# fuse-a-3.net
KiCad netlist of a schematic drawn in EAGLE
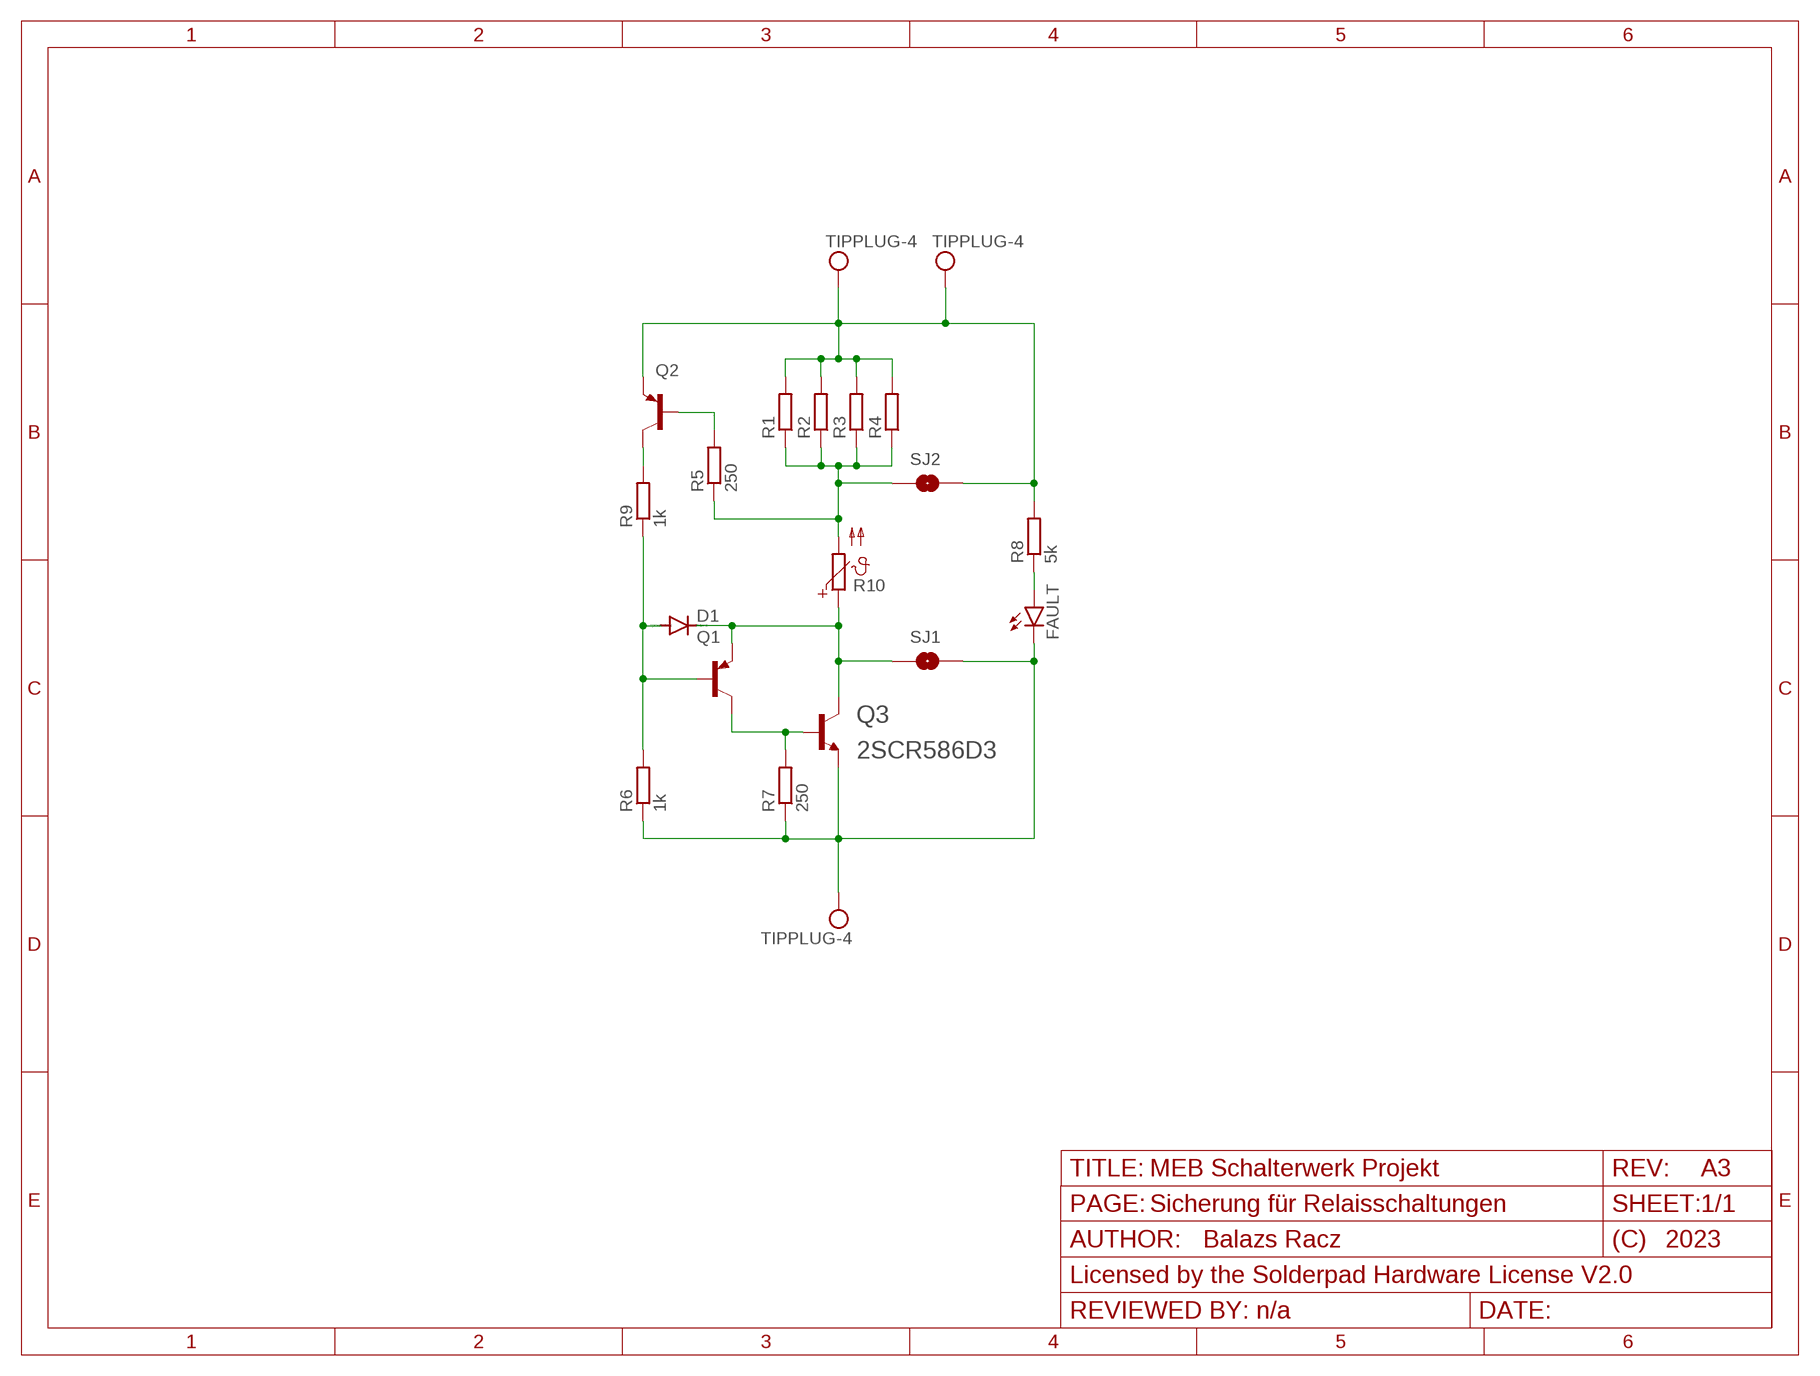
[diagram p0: schematic, sheet 1]

(export (version "E")
  (design (tool "Eeschema 10.0.6"))
  (components
    (comp (ref "D1")
      (value "DIODE-MINIMELF")
      (footprint "eagle-import:MINIMELF")
      (libsource (lib "eagle-import") (part "DIODE-MINIMELF"))
    )
    (comp (ref "FAULT")
      (value "LEDCHIPLED_0603")
      (footprint "eagle-import:CHIPLED_0603")
      (libsource (lib "eagle-import") (part "LEDCHIPLED_0603"))
    )
    (comp (ref "Q1")
      (value "BCX71SMD")
      (footprint "eagle-import:SOT23")
      (libsource (lib "eagle-import") (part "BCX71SMD"))
    )
    (comp (ref "Q2")
      (value "BCX71SMD")
      (footprint "eagle-import:SOT23")
      (libsource (lib "eagle-import") (part "BCX71SMD"))
    )
    (comp (ref "Q3")
      (value "2SCR586D3")
      (footprint "eagle-import:D-PAK_TO252AA")
      (libsource (lib "eagle-import") (part "2SCR586D3TL1"))
    )
    (comp (ref "R1")
      (value "R-EU_R2512")
      (footprint "eagle-import:R2512")
      (libsource (lib "eagle-import") (part "R-EU_R2512"))
    )
    (comp (ref "R2")
      (value "R-EU_R2512")
      (footprint "eagle-import:R2512")
      (libsource (lib "eagle-import") (part "R-EU_R2512"))
    )
    (comp (ref "R3")
      (value "R-EU_R2512")
      (footprint "eagle-import:R2512")
      (libsource (lib "eagle-import") (part "R-EU_R2512"))
    )
    (comp (ref "R4")
      (value "R-EU_R2512")
      (footprint "eagle-import:R2512")
      (libsource (lib "eagle-import") (part "R-EU_R2512"))
    )
    (comp (ref "R5")
      (value "250")
      (footprint "eagle-import:R0805")
      (libsource (lib "eagle-import") (part "R-EU_R0805"))
    )
    (comp (ref "R6")
      (value "1k")
      (footprint "eagle-import:R0805")
      (libsource (lib "eagle-import") (part "R-EU_R0805"))
    )
    (comp (ref "R7")
      (value "250")
      (footprint "eagle-import:R0805")
      (libsource (lib "eagle-import") (part "R-EU_R0805"))
    )
    (comp (ref "R8")
      (value "5k")
      (footprint "eagle-import:R0805")
      (libsource (lib "eagle-import") (part "R-EU_R0805"))
    )
    (comp (ref "R9")
      (value "1k")
      (footprint "eagle-import:R0805")
      (libsource (lib "eagle-import") (part "R-EU_R0805"))
    )
    (comp (ref "R10")
      (value "PTC_1812")
      (footprint "eagle-import:PTC1812")
      (libsource (lib "eagle-import") (part "PTC_1812"))
    )
    (comp (ref "SJ1")
      (value "SJRND2")
      (footprint "eagle-import:SJ_RND2")
      (libsource (lib "eagle-import") (part "SJRND2"))
    )
    (comp (ref "SJ2")
      (value "SJRND2")
      (footprint "eagle-import:SJ_RND2")
      (libsource (lib "eagle-import") (part "SJRND2"))
    )
    (comp (ref "U$1")
      (value "TIPPLUG-4")
      (footprint "eagle-import:BANANAPLUG-4-LUG")
      (libsource (lib "eagle-import") (part "TIPPLUG-4"))
    )
    (comp (ref "U$2")
      (value "TIPPLUG-4")
      (footprint "eagle-import:BANANAPLUG-4-LUG")
      (libsource (lib "eagle-import") (part "TIPPLUG-4"))
    )
    (comp (ref "U$4")
      (value "TIPPLUG-4")
      (footprint "eagle-import:BANANAPLUG-4-LUG")
      (libsource (lib "eagle-import") (part "TIPPLUG-4"))
    )
  )
  (nets
    (net (code "1") (name "Net-(FAULT-PadA)") (class "Default")
      (node (ref "FAULT") (pin "A") (pinfunction "A_A") (pintype "passive"))
      (node (ref "R8") (pin "1") (pinfunction "1_1") (pintype "passive"))
    )
    (net (code "2") (name "Net-(Q1-B)") (class "Default")
      (node (ref "D1") (pin "A") (pinfunction "A_A") (pintype "passive"))
      (node (ref "Q1") (pin "1") (pinfunction "B_1") (pintype "passive"))
      (node (ref "R6") (pin "2") (pinfunction "2_2") (pintype "passive"))
      (node (ref "R9") (pin "1") (pinfunction "1_1") (pintype "passive"))
    )
    (net (code "3") (name "Net-(Q1-C)") (class "Default")
      (node (ref "Q1") (pin "3") (pinfunction "C_3") (pintype "passive"))
      (node (ref "Q3") (pin "1") (pinfunction "B_1") (pintype "passive"))
      (node (ref "R7") (pin "2") (pinfunction "2_2") (pintype "passive"))
    )
    (net (code "4") (name "Net-(Q1-E)") (class "Default")
      (node (ref "D1") (pin "C") (pinfunction "C_C") (pintype "passive"))
      (node (ref "Q1") (pin "2") (pinfunction "E_2") (pintype "passive"))
      (node (ref "Q3") (pin "4") (pinfunction "C_4") (pintype "passive"))
      (node (ref "R10") (pin "1") (pinfunction "1_1") (pintype "passive"))
      (node (ref "SJ1") (pin "P$1") (pinfunction "1_P$1") (pintype "passive"))
    )
    (net (code "5") (name "Net-(Q2-B)") (class "Default")
      (node (ref "Q2") (pin "1") (pinfunction "B_1") (pintype "passive"))
      (node (ref "R5") (pin "2") (pinfunction "2_2") (pintype "passive"))
    )
    (net (code "6") (name "Net-(Q2-C)") (class "Default")
      (node (ref "Q2") (pin "3") (pinfunction "C_3") (pintype "passive"))
      (node (ref "R9") (pin "2") (pinfunction "2_2") (pintype "passive"))
    )
    (net (code "7") (name "Net-(Q2-E)") (class "Default")
      (node (ref "Q2") (pin "2") (pinfunction "E_2") (pintype "passive"))
      (node (ref "R1") (pin "2") (pinfunction "2_2") (pintype "passive"))
      (node (ref "R2") (pin "2") (pinfunction "2_2") (pintype "passive"))
      (node (ref "R3") (pin "2") (pinfunction "2_2") (pintype "passive"))
      (node (ref "R4") (pin "2") (pinfunction "2_2") (pintype "passive"))
      (node (ref "R8") (pin "2") (pinfunction "2_2") (pintype "passive"))
      (node (ref "SJ2") (pin "P$2") (pinfunction "2_P$2") (pintype "passive"))
      (node (ref "U$1") (pin "4MM") (pinfunction "$1_4MM") (pintype "passive"))
      (node (ref "U$4") (pin "4MM") (pinfunction "$1_4MM") (pintype "passive"))
    )
    (net (code "8") (name "Net-(Q3-E)") (class "Default")
      (node (ref "FAULT") (pin "C") (pinfunction "C_C") (pintype "passive"))
      (node (ref "Q3") (pin "3") (pinfunction "E_3") (pintype "passive"))
      (node (ref "R6") (pin "1") (pinfunction "1_1") (pintype "passive"))
      (node (ref "R7") (pin "1") (pinfunction "1_1") (pintype "passive"))
      (node (ref "SJ1") (pin "P$2") (pinfunction "2_P$2") (pintype "passive"))
      (node (ref "U$2") (pin "4MM") (pinfunction "$1_4MM") (pintype "passive"))
    )
    (net (code "9") (name "Net-(SJ2-1)") (class "Default")
      (node (ref "R1") (pin "1") (pinfunction "1_1") (pintype "passive"))
      (node (ref "R10") (pin "2") (pinfunction "2_2") (pintype "passive"))
      (node (ref "R2") (pin "1") (pinfunction "1_1") (pintype "passive"))
      (node (ref "R3") (pin "1") (pinfunction "1_1") (pintype "passive"))
      (node (ref "R4") (pin "1") (pinfunction "1_1") (pintype "passive"))
      (node (ref "R5") (pin "1") (pinfunction "1_1") (pintype "passive"))
      (node (ref "SJ2") (pin "P$1") (pinfunction "1_P$1") (pintype "passive"))
    )
  )
)
